# SCH_Trail-PCB_2024-05-27.net
KiCad netlist of a schematic drawn in EasyEDA
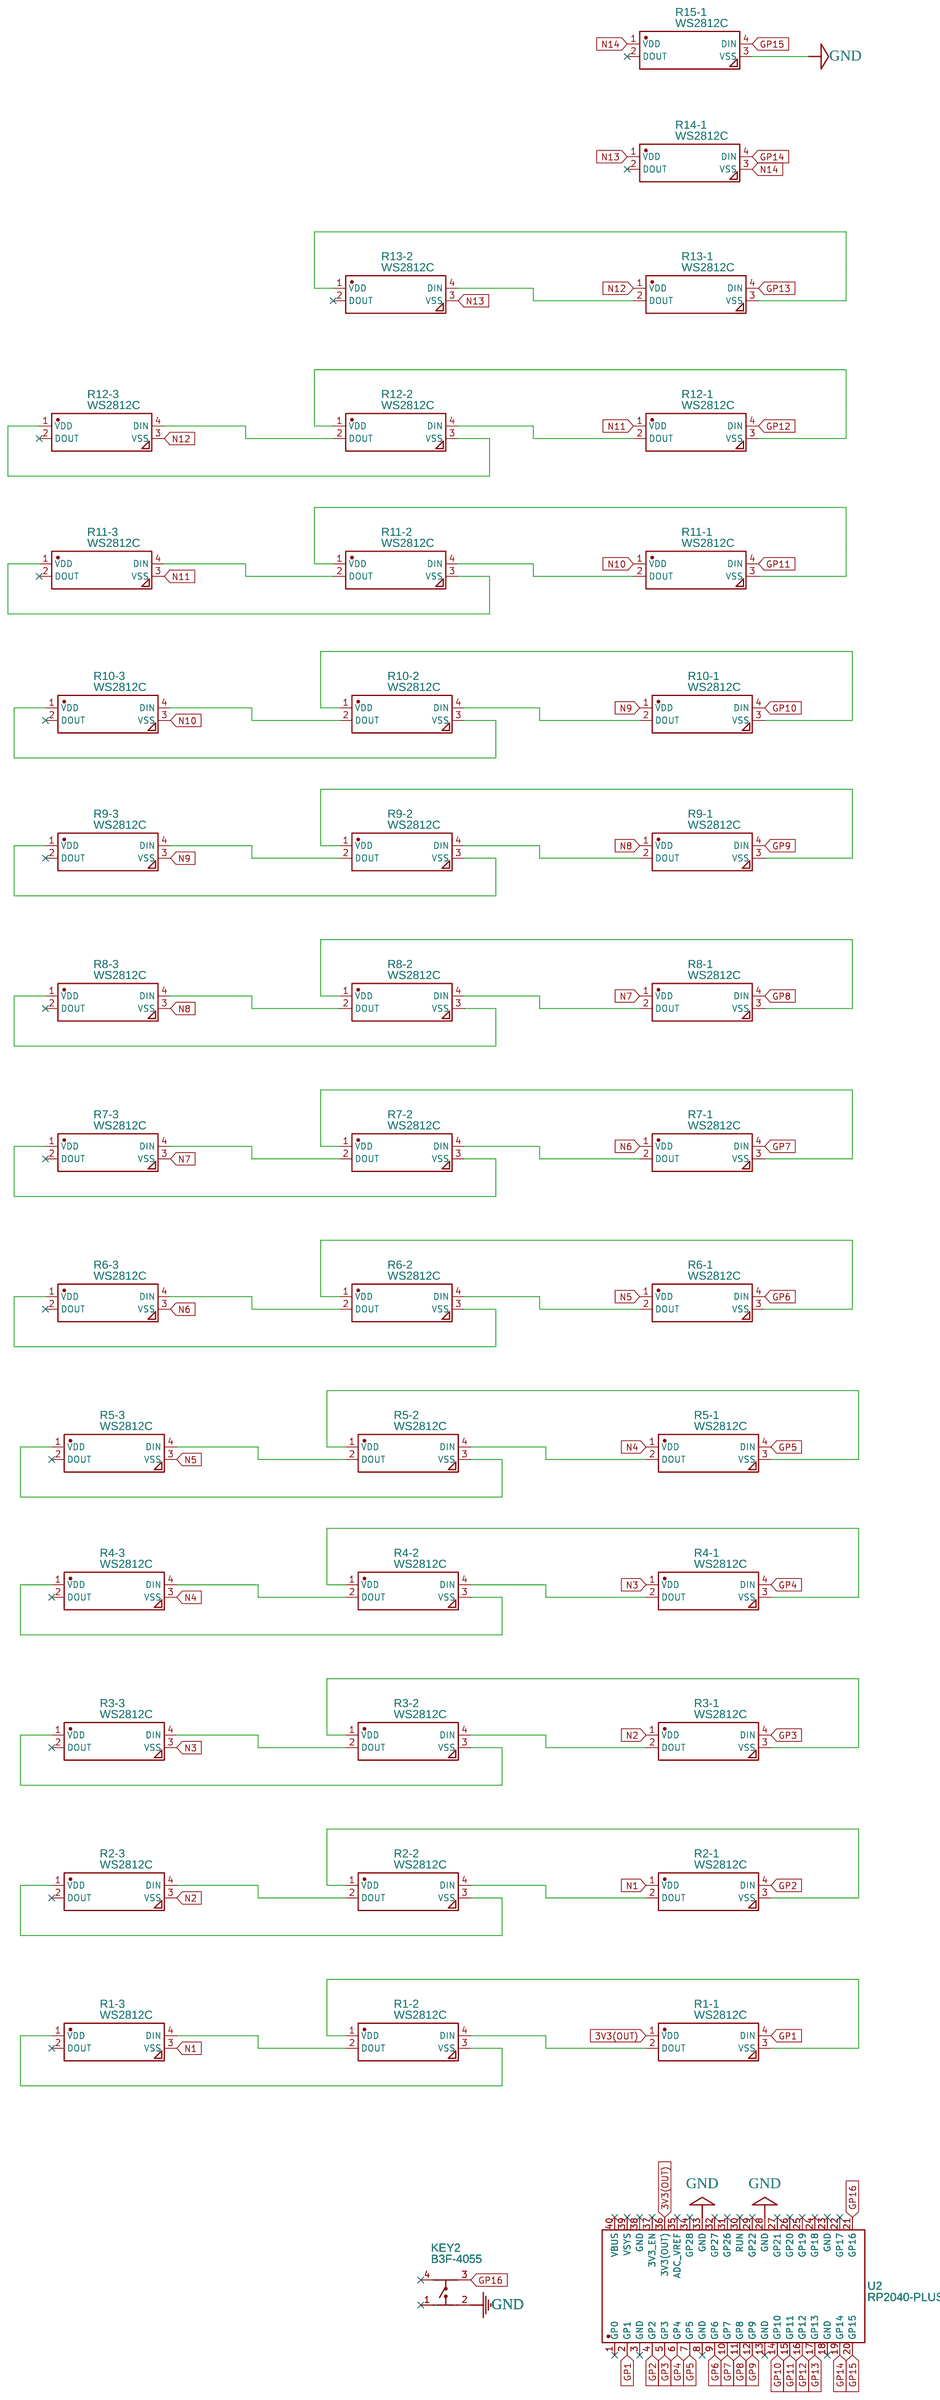
[diagram p0: Sheet_1]
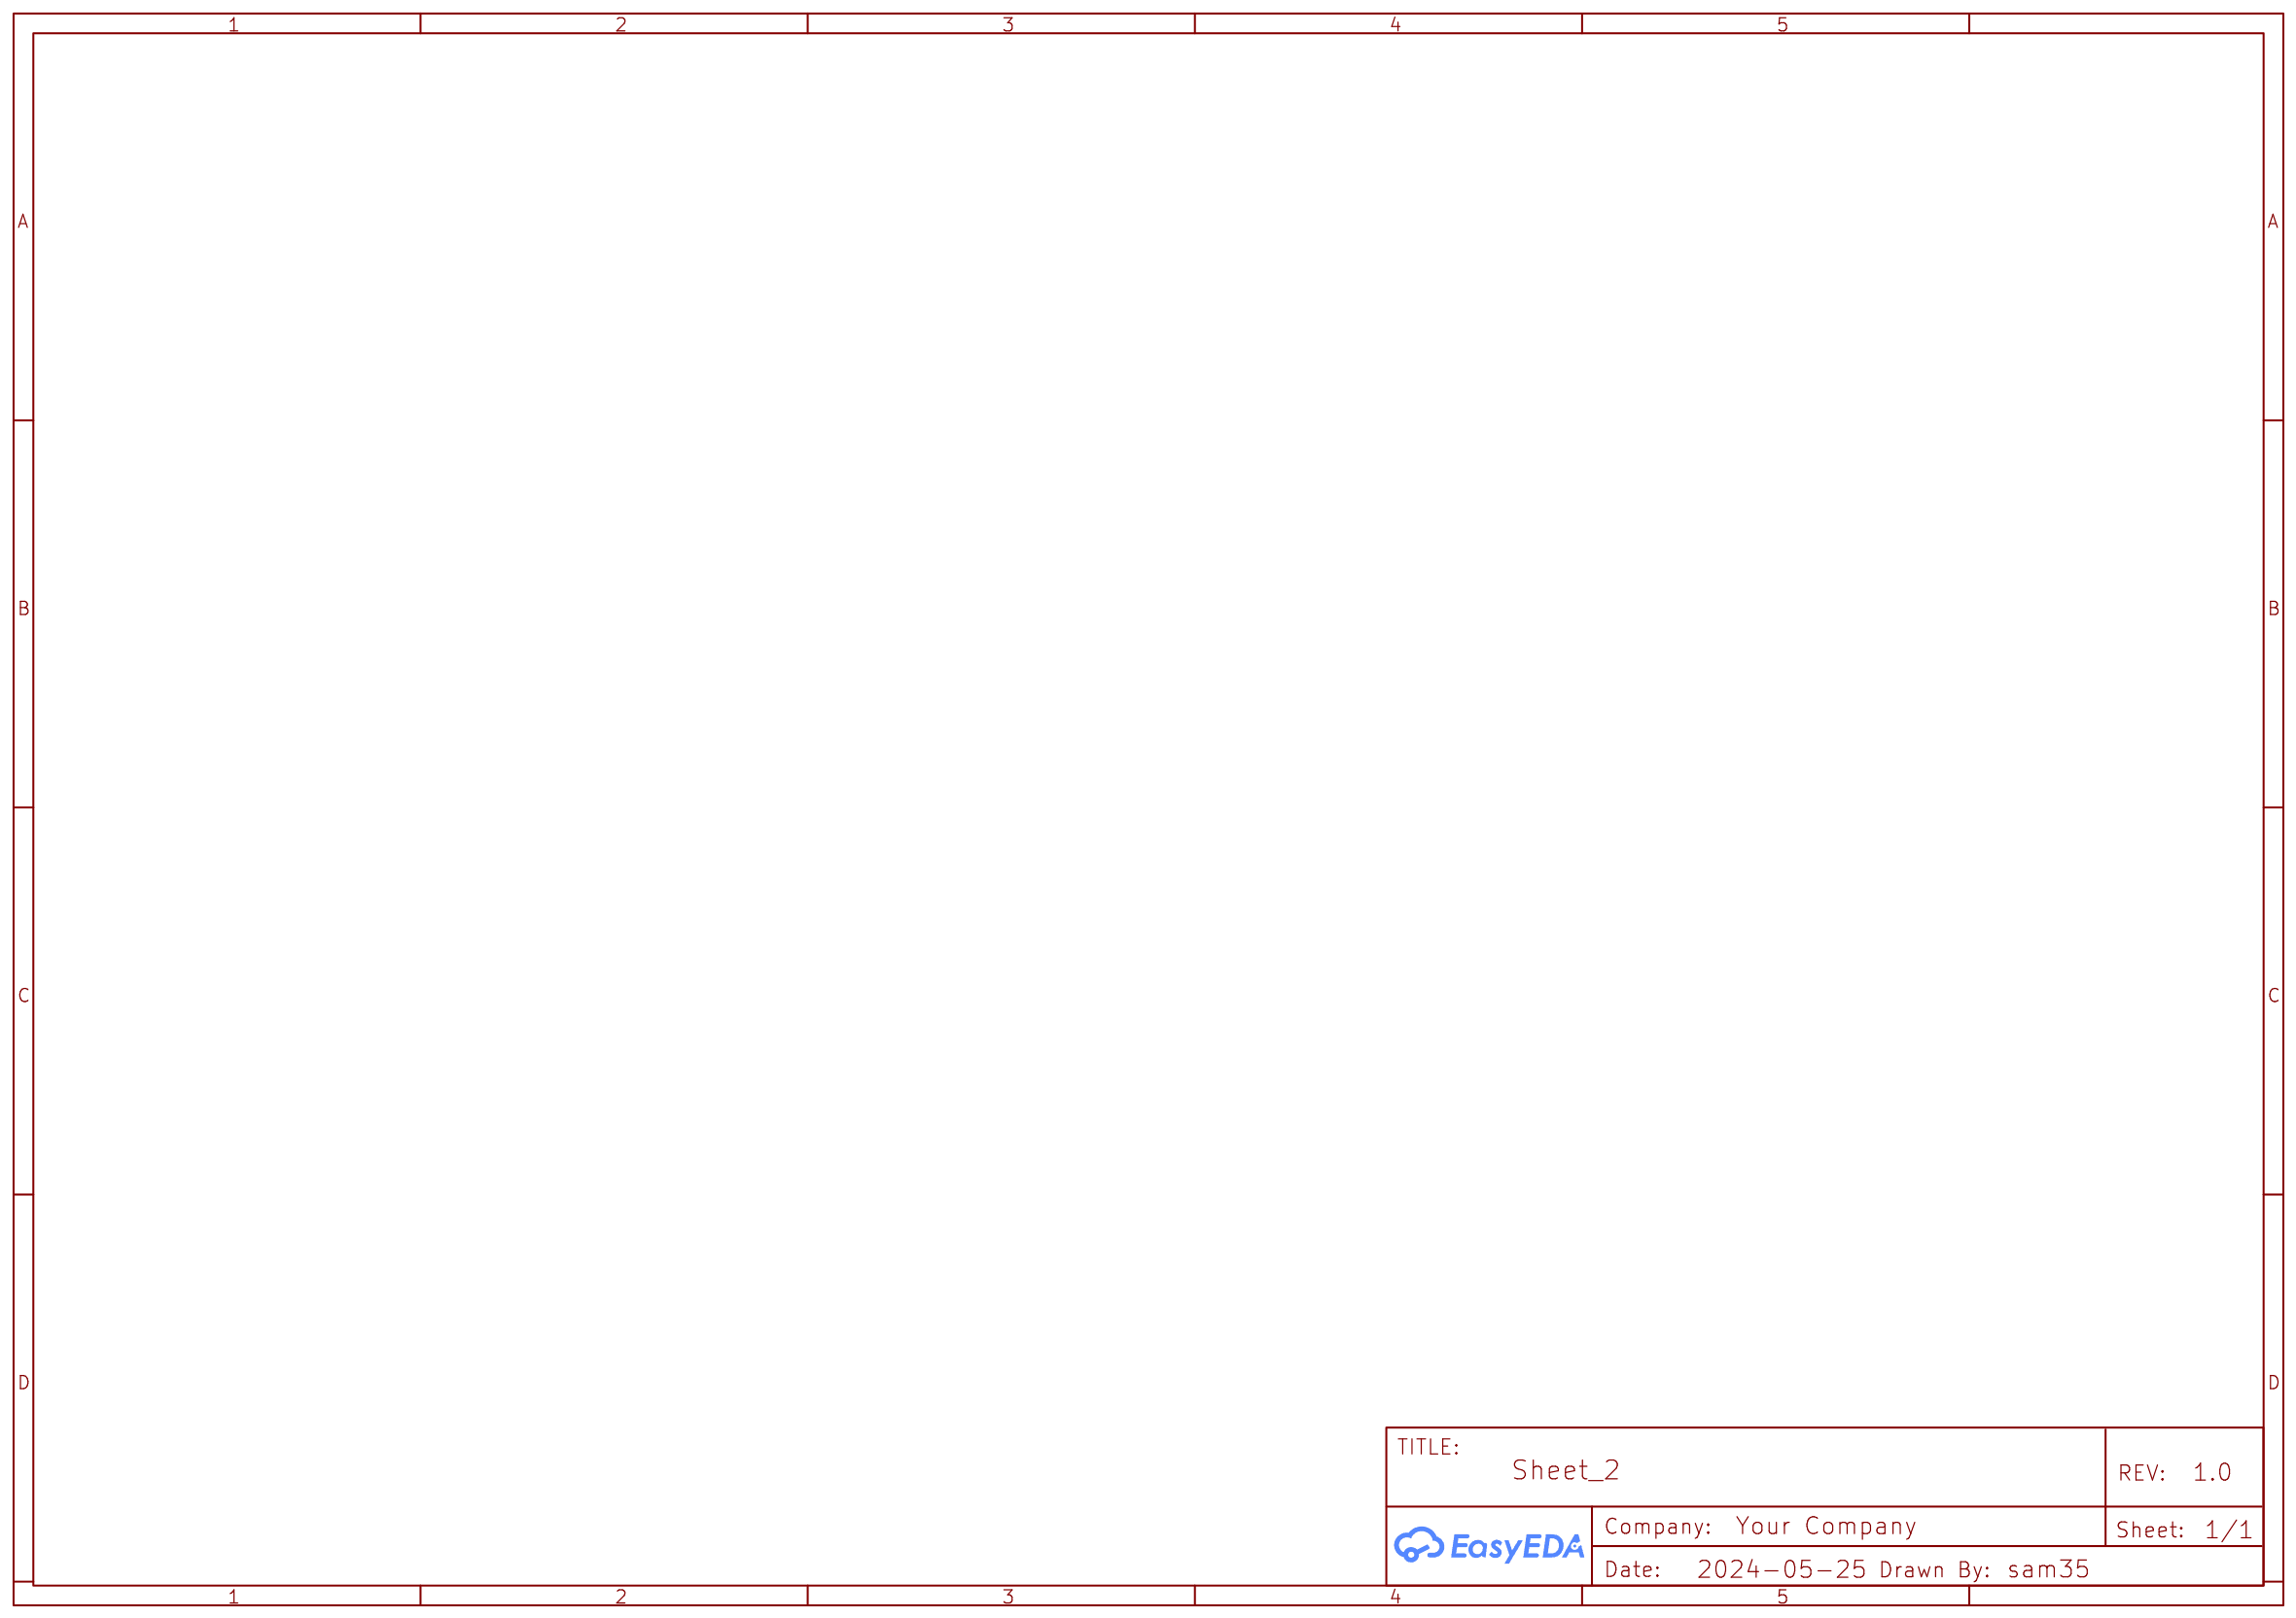
[diagram p1: Sheet_2]

(export (version "E")
  (design (tool "Eeschema 10.0.6"))
  (components
    (comp (ref "KEY2")
      (value "B3F-4055")
      (fields (field (name "Manufacturer") "OMRON(欧姆龙)"))
      (libsource (lib "") (part "B3F-4055"))
    )
    (comp (ref "R1-1")
      (value "WS2812C")
      (fields (field (name "Manufacturer") "worldsemi"))
      (libsource (lib "") (part "WS2812C_4"))
    )
    (comp (ref "R1-2")
      (value "WS2812C")
      (fields (field (name "Manufacturer") "worldsemi"))
      (libsource (lib "") (part "WS2812C_4"))
    )
    (comp (ref "R1-3")
      (value "WS2812C")
      (fields (field (name "Manufacturer") "worldsemi"))
      (libsource (lib "") (part "WS2812C_4"))
    )
    (comp (ref "R2-1")
      (value "WS2812C")
      (fields (field (name "Manufacturer") "worldsemi"))
      (libsource (lib "") (part "WS2812C_8"))
    )
    (comp (ref "R2-2")
      (value "WS2812C")
      (fields (field (name "Manufacturer") "worldsemi"))
      (libsource (lib "") (part "WS2812C_8"))
    )
    (comp (ref "R2-3")
      (value "WS2812C")
      (fields (field (name "Manufacturer") "worldsemi"))
      (libsource (lib "") (part "WS2812C_8"))
    )
    (comp (ref "R3-1")
      (value "WS2812C")
      (fields (field (name "Manufacturer") "worldsemi"))
      (libsource (lib "") (part "WS2812C_3"))
    )
    (comp (ref "R3-2")
      (value "WS2812C")
      (fields (field (name "Manufacturer") "worldsemi"))
      (libsource (lib "") (part "WS2812C_3"))
    )
    (comp (ref "R3-3")
      (value "WS2812C")
      (fields (field (name "Manufacturer") "worldsemi"))
      (libsource (lib "") (part "WS2812C_3"))
    )
    (comp (ref "R4-1")
      (value "WS2812C")
      (fields (field (name "Manufacturer") "worldsemi"))
      (libsource (lib "") (part "WS2812C_6"))
    )
    (comp (ref "R4-2")
      (value "WS2812C")
      (fields (field (name "Manufacturer") "worldsemi"))
      (libsource (lib "") (part "WS2812C_6"))
    )
    (comp (ref "R4-3")
      (value "WS2812C")
      (fields (field (name "Manufacturer") "worldsemi"))
      (libsource (lib "") (part "WS2812C_6"))
    )
    (comp (ref "R5-1")
      (value "WS2812C")
      (fields (field (name "Manufacturer") "worldsemi"))
      (libsource (lib "") (part "WS2812C_1"))
    )
    (comp (ref "R5-2")
      (value "WS2812C")
      (fields (field (name "Manufacturer") "worldsemi"))
      (libsource (lib "") (part "WS2812C_1"))
    )
    (comp (ref "R5-3")
      (value "WS2812C")
      (fields (field (name "Manufacturer") "worldsemi"))
      (libsource (lib "") (part "WS2812C_1"))
    )
    (comp (ref "R6-1")
      (value "WS2812C")
      (fields (field (name "Manufacturer") "worldsemi"))
      (libsource (lib "") (part "WS2812C"))
    )
    (comp (ref "R6-2")
      (value "WS2812C")
      (fields (field (name "Manufacturer") "worldsemi"))
      (libsource (lib "") (part "WS2812C"))
    )
    (comp (ref "R6-3")
      (value "WS2812C")
      (fields (field (name "Manufacturer") "worldsemi"))
      (libsource (lib "") (part "WS2812C"))
    )
    (comp (ref "R7-1")
      (value "WS2812C")
      (fields (field (name "Manufacturer") "worldsemi"))
      (libsource (lib "") (part "WS2812C_7"))
    )
    (comp (ref "R7-2")
      (value "WS2812C")
      (fields (field (name "Manufacturer") "worldsemi"))
      (libsource (lib "") (part "WS2812C_7"))
    )
    (comp (ref "R7-3")
      (value "WS2812C")
      (fields (field (name "Manufacturer") "worldsemi"))
      (libsource (lib "") (part "WS2812C_7"))
    )
    (comp (ref "R8-1")
      (value "WS2812C")
      (fields (field (name "Manufacturer") "worldsemi"))
      (libsource (lib "") (part "WS2812C_9"))
    )
    (comp (ref "R8-2")
      (value "WS2812C")
      (fields (field (name "Manufacturer") "worldsemi"))
      (libsource (lib "") (part "WS2812C_9"))
    )
    (comp (ref "R8-3")
      (value "WS2812C")
      (fields (field (name "Manufacturer") "worldsemi"))
      (libsource (lib "") (part "WS2812C_9"))
    )
    (comp (ref "R9-1")
      (value "WS2812C")
      (fields (field (name "Manufacturer") "worldsemi"))
      (libsource (lib "") (part "WS2812C_11"))
    )
    (comp (ref "R9-2")
      (value "WS2812C")
      (fields (field (name "Manufacturer") "worldsemi"))
      (libsource (lib "") (part "WS2812C_11"))
    )
    (comp (ref "R9-3")
      (value "WS2812C")
      (fields (field (name "Manufacturer") "worldsemi"))
      (libsource (lib "") (part "WS2812C_11"))
    )
    (comp (ref "R10-1")
      (value "WS2812C")
      (fields (field (name "Manufacturer") "worldsemi"))
      (libsource (lib "") (part "WS2812C_12"))
    )
    (comp (ref "R10-2")
      (value "WS2812C")
      (fields (field (name "Manufacturer") "worldsemi"))
      (libsource (lib "") (part "WS2812C_12"))
    )
    (comp (ref "R10-3")
      (value "WS2812C")
      (fields (field (name "Manufacturer") "worldsemi"))
      (libsource (lib "") (part "WS2812C_12"))
    )
    (comp (ref "R11-1")
      (value "WS2812C")
      (fields (field (name "Manufacturer") "worldsemi"))
      (libsource (lib "") (part "WS2812C_2"))
    )
    (comp (ref "R11-2")
      (value "WS2812C")
      (fields (field (name "Manufacturer") "worldsemi"))
      (libsource (lib "") (part "WS2812C_2"))
    )
    (comp (ref "R11-3")
      (value "WS2812C")
      (fields (field (name "Manufacturer") "worldsemi"))
      (libsource (lib "") (part "WS2812C_2"))
    )
    (comp (ref "R12-1")
      (value "WS2812C")
      (fields (field (name "Manufacturer") "worldsemi"))
      (libsource (lib "") (part "WS2812C_5"))
    )
    (comp (ref "R12-2")
      (value "WS2812C")
      (fields (field (name "Manufacturer") "worldsemi"))
      (libsource (lib "") (part "WS2812C_5"))
    )
    (comp (ref "R12-3")
      (value "WS2812C")
      (fields (field (name "Manufacturer") "worldsemi"))
      (libsource (lib "") (part "WS2812C_5"))
    )
    (comp (ref "R13-1")
      (value "WS2812C")
      (fields (field (name "Manufacturer") "worldsemi"))
      (libsource (lib "") (part "WS2812C_13"))
    )
    (comp (ref "R13-2")
      (value "WS2812C")
      (fields (field (name "Manufacturer") "worldsemi"))
      (libsource (lib "") (part "WS2812C_13"))
    )
    (comp (ref "R14-1")
      (value "WS2812C")
      (fields (field (name "Manufacturer") "worldsemi"))
      (libsource (lib "") (part "WS2812C_14"))
    )
    (comp (ref "R15-1")
      (value "WS2812C")
      (fields (field (name "Manufacturer") "worldsemi"))
      (libsource (lib "") (part "WS2812C_10"))
    )
    (comp (ref "U2")
      (value "RP2040-PLUS")
      (fields
        (field (name "Manufacturer Part") "RP2040-Plus")
        (field (name "Manufacturer") "Waveshare(微雪电子)")
      )
      (libsource (lib "") (part "RP2040-PLUS"))
    )
  )
  (nets
    (net (code "1") (name "3V3(OUT)") (class "Default")
      (node (ref "R1-1") (pin "1") (pinfunction "VDD_1") (pintype "unspecified"))
      (node (ref "U2") (pin "36") (pinfunction "3V3(OUT)_36") (pintype "unspecified"))
    )
    (net (code "2") (name "GND") (class "Default")
      (node (ref "KEY2") (pin "2") (pinfunction "2_2") (pintype "unspecified"))
      (node (ref "R15-1") (pin "3") (pinfunction "VSS_3") (pintype "unspecified"))
      (node (ref "U2") (pin "28") (pinfunction "GND_28") (pintype "unspecified"))
      (node (ref "U2") (pin "33") (pinfunction "GND_33") (pintype "unspecified"))
    )
    (net (code "3") (name "GP1") (class "Default")
      (node (ref "R1-1") (pin "4") (pinfunction "DIN_4") (pintype "unspecified"))
      (node (ref "U2") (pin "2") (pinfunction "GP1_2") (pintype "unspecified"))
    )
    (net (code "4") (name "GP2") (class "Default")
      (node (ref "R2-1") (pin "4") (pinfunction "DIN_4") (pintype "unspecified"))
      (node (ref "U2") (pin "4") (pinfunction "GP2_4") (pintype "unspecified"))
    )
    (net (code "5") (name "GP3") (class "Default")
      (node (ref "R3-1") (pin "4") (pinfunction "DIN_4") (pintype "unspecified"))
      (node (ref "U2") (pin "5") (pinfunction "GP3_5") (pintype "unspecified"))
    )
    (net (code "6") (name "GP4") (class "Default")
      (node (ref "R4-1") (pin "4") (pinfunction "DIN_4") (pintype "unspecified"))
      (node (ref "U2") (pin "6") (pinfunction "GP4_6") (pintype "unspecified"))
    )
    (net (code "7") (name "GP5") (class "Default")
      (node (ref "R5-1") (pin "4") (pinfunction "DIN_4") (pintype "unspecified"))
      (node (ref "U2") (pin "7") (pinfunction "GP5_7") (pintype "unspecified"))
    )
    (net (code "8") (name "GP6") (class "Default")
      (node (ref "R6-1") (pin "4") (pinfunction "DIN_4") (pintype "unspecified"))
      (node (ref "U2") (pin "9") (pinfunction "GP6_9") (pintype "unspecified"))
    )
    (net (code "9") (name "GP7") (class "Default")
      (node (ref "R7-1") (pin "4") (pinfunction "DIN_4") (pintype "unspecified"))
      (node (ref "U2") (pin "10") (pinfunction "GP7_10") (pintype "unspecified"))
    )
    (net (code "10") (name "GP8") (class "Default")
      (node (ref "R8-1") (pin "4") (pinfunction "DIN_4") (pintype "unspecified"))
      (node (ref "U2") (pin "11") (pinfunction "GP8_11") (pintype "unspecified"))
    )
    (net (code "11") (name "GP9") (class "Default")
      (node (ref "R9-1") (pin "4") (pinfunction "DIN_4") (pintype "unspecified"))
      (node (ref "U2") (pin "12") (pinfunction "GP9_12") (pintype "unspecified"))
    )
    (net (code "12") (name "GP10") (class "Default")
      (node (ref "R10-1") (pin "4") (pinfunction "DIN_4") (pintype "unspecified"))
      (node (ref "U2") (pin "14") (pinfunction "GP10_14") (pintype "unspecified"))
    )
    (net (code "13") (name "GP11") (class "Default")
      (node (ref "R11-1") (pin "4") (pinfunction "DIN_4") (pintype "unspecified"))
      (node (ref "U2") (pin "15") (pinfunction "GP11_15") (pintype "unspecified"))
    )
    (net (code "14") (name "GP12") (class "Default")
      (node (ref "R12-1") (pin "4") (pinfunction "DIN_4") (pintype "unspecified"))
      (node (ref "U2") (pin "16") (pinfunction "GP12_16") (pintype "unspecified"))
    )
    (net (code "15") (name "GP13") (class "Default")
      (node (ref "R13-1") (pin "4") (pinfunction "DIN_4") (pintype "unspecified"))
      (node (ref "U2") (pin "17") (pinfunction "GP13_17") (pintype "unspecified"))
    )
    (net (code "16") (name "GP14") (class "Default")
      (node (ref "R14-1") (pin "4") (pinfunction "DIN_4") (pintype "unspecified"))
      (node (ref "U2") (pin "19") (pinfunction "GP14_19") (pintype "unspecified"))
    )
    (net (code "17") (name "GP15") (class "Default")
      (node (ref "R15-1") (pin "4") (pinfunction "DIN_4") (pintype "unspecified"))
      (node (ref "U2") (pin "20") (pinfunction "GP15_20") (pintype "unspecified"))
    )
    (net (code "18") (name "GP16") (class "Default")
      (node (ref "KEY2") (pin "3") (pinfunction "3_3") (pintype "unspecified"))
      (node (ref "U2") (pin "21") (pinfunction "GP16_21") (pintype "unspecified"))
    )
    (net (code "19") (name "N1") (class "Default")
      (node (ref "R1-3") (pin "3") (pinfunction "VSS_3") (pintype "unspecified"))
      (node (ref "R2-1") (pin "1") (pinfunction "VDD_1") (pintype "unspecified"))
    )
    (net (code "20") (name "N2") (class "Default")
      (node (ref "R2-3") (pin "3") (pinfunction "VSS_3") (pintype "unspecified"))
      (node (ref "R3-1") (pin "1") (pinfunction "VDD_1") (pintype "unspecified"))
    )
    (net (code "21") (name "N3") (class "Default")
      (node (ref "R3-3") (pin "3") (pinfunction "VSS_3") (pintype "unspecified"))
      (node (ref "R4-1") (pin "1") (pinfunction "VDD_1") (pintype "unspecified"))
    )
    (net (code "22") (name "N4") (class "Default")
      (node (ref "R4-3") (pin "3") (pinfunction "VSS_3") (pintype "unspecified"))
      (node (ref "R5-1") (pin "1") (pinfunction "VDD_1") (pintype "unspecified"))
    )
    (net (code "23") (name "N5") (class "Default")
      (node (ref "R5-3") (pin "3") (pinfunction "VSS_3") (pintype "unspecified"))
      (node (ref "R6-1") (pin "1") (pinfunction "VDD_1") (pintype "unspecified"))
    )
    (net (code "24") (name "N6") (class "Default")
      (node (ref "R6-3") (pin "3") (pinfunction "VSS_3") (pintype "unspecified"))
      (node (ref "R7-1") (pin "1") (pinfunction "VDD_1") (pintype "unspecified"))
    )
    (net (code "25") (name "N7") (class "Default")
      (node (ref "R7-3") (pin "3") (pinfunction "VSS_3") (pintype "unspecified"))
      (node (ref "R8-1") (pin "1") (pinfunction "VDD_1") (pintype "unspecified"))
    )
    (net (code "26") (name "N8") (class "Default")
      (node (ref "R8-3") (pin "3") (pinfunction "VSS_3") (pintype "unspecified"))
      (node (ref "R9-1") (pin "1") (pinfunction "VDD_1") (pintype "unspecified"))
    )
    (net (code "27") (name "N9") (class "Default")
      (node (ref "R10-1") (pin "1") (pinfunction "VDD_1") (pintype "unspecified"))
      (node (ref "R9-3") (pin "3") (pinfunction "VSS_3") (pintype "unspecified"))
    )
    (net (code "28") (name "N10") (class "Default")
      (node (ref "R10-3") (pin "3") (pinfunction "VSS_3") (pintype "unspecified"))
      (node (ref "R11-1") (pin "1") (pinfunction "VDD_1") (pintype "unspecified"))
    )
    (net (code "29") (name "N11") (class "Default")
      (node (ref "R11-3") (pin "3") (pinfunction "VSS_3") (pintype "unspecified"))
      (node (ref "R12-1") (pin "1") (pinfunction "VDD_1") (pintype "unspecified"))
    )
    (net (code "30") (name "N12") (class "Default")
      (node (ref "R12-3") (pin "3") (pinfunction "VSS_3") (pintype "unspecified"))
      (node (ref "R13-1") (pin "1") (pinfunction "VDD_1") (pintype "unspecified"))
    )
    (net (code "31") (name "N13") (class "Default")
      (node (ref "R13-2") (pin "3") (pinfunction "VSS_3") (pintype "unspecified"))
      (node (ref "R14-1") (pin "1") (pinfunction "VDD_1") (pintype "unspecified"))
    )
    (net (code "32") (name "N14") (class "Default")
      (node (ref "R14-1") (pin "3") (pinfunction "VSS_3") (pintype "unspecified"))
      (node (ref "R15-1") (pin "1") (pinfunction "VDD_1") (pintype "unspecified"))
    )
    (net (code "33") (name "Net-(R1-1-DOUT)") (class "Default")
      (node (ref "R1-1") (pin "2") (pinfunction "DOUT_2") (pintype "unspecified"))
      (node (ref "R1-2") (pin "4") (pinfunction "DIN_4") (pintype "unspecified"))
    )
    (net (code "34") (name "Net-(R1-1-VSS)") (class "Default")
      (node (ref "R1-1") (pin "3") (pinfunction "VSS_3") (pintype "unspecified"))
      (node (ref "R1-2") (pin "1") (pinfunction "VDD_1") (pintype "unspecified"))
    )
    (net (code "35") (name "Net-(R1-2-DOUT)") (class "Default")
      (node (ref "R1-2") (pin "2") (pinfunction "DOUT_2") (pintype "unspecified"))
      (node (ref "R1-3") (pin "4") (pinfunction "DIN_4") (pintype "unspecified"))
    )
    (net (code "36") (name "Net-(R1-2-VSS)") (class "Default")
      (node (ref "R1-2") (pin "3") (pinfunction "VSS_3") (pintype "unspecified"))
      (node (ref "R1-3") (pin "1") (pinfunction "VDD_1") (pintype "unspecified"))
    )
    (net (code "37") (name "Net-(R2-1-DOUT)") (class "Default")
      (node (ref "R2-1") (pin "2") (pinfunction "DOUT_2") (pintype "unspecified"))
      (node (ref "R2-2") (pin "4") (pinfunction "DIN_4") (pintype "unspecified"))
    )
    (net (code "38") (name "Net-(R2-1-VSS)") (class "Default")
      (node (ref "R2-1") (pin "3") (pinfunction "VSS_3") (pintype "unspecified"))
      (node (ref "R2-2") (pin "1") (pinfunction "VDD_1") (pintype "unspecified"))
    )
    (net (code "39") (name "Net-(R2-2-DOUT)") (class "Default")
      (node (ref "R2-2") (pin "2") (pinfunction "DOUT_2") (pintype "unspecified"))
      (node (ref "R2-3") (pin "4") (pinfunction "DIN_4") (pintype "unspecified"))
    )
    (net (code "40") (name "Net-(R2-2-VSS)") (class "Default")
      (node (ref "R2-2") (pin "3") (pinfunction "VSS_3") (pintype "unspecified"))
      (node (ref "R2-3") (pin "1") (pinfunction "VDD_1") (pintype "unspecified"))
    )
    (net (code "41") (name "Net-(R3-1-DOUT)") (class "Default")
      (node (ref "R3-1") (pin "2") (pinfunction "DOUT_2") (pintype "unspecified"))
      (node (ref "R3-2") (pin "4") (pinfunction "DIN_4") (pintype "unspecified"))
    )
    (net (code "42") (name "Net-(R3-1-VSS)") (class "Default")
      (node (ref "R3-1") (pin "3") (pinfunction "VSS_3") (pintype "unspecified"))
      (node (ref "R3-2") (pin "1") (pinfunction "VDD_1") (pintype "unspecified"))
    )
    (net (code "43") (name "Net-(R3-2-DOUT)") (class "Default")
      (node (ref "R3-2") (pin "2") (pinfunction "DOUT_2") (pintype "unspecified"))
      (node (ref "R3-3") (pin "4") (pinfunction "DIN_4") (pintype "unspecified"))
    )
    (net (code "44") (name "Net-(R3-2-VSS)") (class "Default")
      (node (ref "R3-2") (pin "3") (pinfunction "VSS_3") (pintype "unspecified"))
      (node (ref "R3-3") (pin "1") (pinfunction "VDD_1") (pintype "unspecified"))
    )
    (net (code "45") (name "Net-(R4-1-DOUT)") (class "Default")
      (node (ref "R4-1") (pin "2") (pinfunction "DOUT_2") (pintype "unspecified"))
      (node (ref "R4-2") (pin "4") (pinfunction "DIN_4") (pintype "unspecified"))
    )
    (net (code "46") (name "Net-(R4-1-VSS)") (class "Default")
      (node (ref "R4-1") (pin "3") (pinfunction "VSS_3") (pintype "unspecified"))
      (node (ref "R4-2") (pin "1") (pinfunction "VDD_1") (pintype "unspecified"))
    )
    (net (code "47") (name "Net-(R4-2-DOUT)") (class "Default")
      (node (ref "R4-2") (pin "2") (pinfunction "DOUT_2") (pintype "unspecified"))
      (node (ref "R4-3") (pin "4") (pinfunction "DIN_4") (pintype "unspecified"))
    )
    (net (code "48") (name "Net-(R4-2-VSS)") (class "Default")
      (node (ref "R4-2") (pin "3") (pinfunction "VSS_3") (pintype "unspecified"))
      (node (ref "R4-3") (pin "1") (pinfunction "VDD_1") (pintype "unspecified"))
    )
    (net (code "49") (name "Net-(R5-1-DOUT)") (class "Default")
      (node (ref "R5-1") (pin "2") (pinfunction "DOUT_2") (pintype "unspecified"))
      (node (ref "R5-2") (pin "4") (pinfunction "DIN_4") (pintype "unspecified"))
    )
    (net (code "50") (name "Net-(R5-1-VSS)") (class "Default")
      (node (ref "R5-1") (pin "3") (pinfunction "VSS_3") (pintype "unspecified"))
      (node (ref "R5-2") (pin "1") (pinfunction "VDD_1") (pintype "unspecified"))
    )
    (net (code "51") (name "Net-(R5-2-DOUT)") (class "Default")
      (node (ref "R5-2") (pin "2") (pinfunction "DOUT_2") (pintype "unspecified"))
      (node (ref "R5-3") (pin "4") (pinfunction "DIN_4") (pintype "unspecified"))
    )
    (net (code "52") (name "Net-(R5-2-VSS)") (class "Default")
      (node (ref "R5-2") (pin "3") (pinfunction "VSS_3") (pintype "unspecified"))
      (node (ref "R5-3") (pin "1") (pinfunction "VDD_1") (pintype "unspecified"))
    )
    (net (code "53") (name "Net-(R6-1-DOUT)") (class "Default")
      (node (ref "R6-1") (pin "2") (pinfunction "DOUT_2") (pintype "unspecified"))
      (node (ref "R6-2") (pin "4") (pinfunction "DIN_4") (pintype "unspecified"))
    )
    (net (code "54") (name "Net-(R6-1-VSS)") (class "Default")
      (node (ref "R6-1") (pin "3") (pinfunction "VSS_3") (pintype "unspecified"))
      (node (ref "R6-2") (pin "1") (pinfunction "VDD_1") (pintype "unspecified"))
    )
    (net (code "55") (name "Net-(R6-2-DOUT)") (class "Default")
      (node (ref "R6-2") (pin "2") (pinfunction "DOUT_2") (pintype "unspecified"))
      (node (ref "R6-3") (pin "4") (pinfunction "DIN_4") (pintype "unspecified"))
    )
    (net (code "56") (name "Net-(R6-2-VSS)") (class "Default")
      (node (ref "R6-2") (pin "3") (pinfunction "VSS_3") (pintype "unspecified"))
      (node (ref "R6-3") (pin "1") (pinfunction "VDD_1") (pintype "unspecified"))
    )
    (net (code "57") (name "Net-(R7-1-DOUT)") (class "Default")
      (node (ref "R7-1") (pin "2") (pinfunction "DOUT_2") (pintype "unspecified"))
      (node (ref "R7-2") (pin "4") (pinfunction "DIN_4") (pintype "unspecified"))
    )
    (net (code "58") (name "Net-(R7-1-VSS)") (class "Default")
      (node (ref "R7-1") (pin "3") (pinfunction "VSS_3") (pintype "unspecified"))
      (node (ref "R7-2") (pin "1") (pinfunction "VDD_1") (pintype "unspecified"))
    )
    (net (code "59") (name "Net-(R7-2-DOUT)") (class "Default")
      (node (ref "R7-2") (pin "2") (pinfunction "DOUT_2") (pintype "unspecified"))
      (node (ref "R7-3") (pin "4") (pinfunction "DIN_4") (pintype "unspecified"))
    )
    (net (code "60") (name "Net-(R7-2-VSS)") (class "Default")
      (node (ref "R7-2") (pin "3") (pinfunction "VSS_3") (pintype "unspecified"))
      (node (ref "R7-3") (pin "1") (pinfunction "VDD_1") (pintype "unspecified"))
    )
    (net (code "61") (name "Net-(R8-1-DOUT)") (class "Default")
      (node (ref "R8-1") (pin "2") (pinfunction "DOUT_2") (pintype "unspecified"))
      (node (ref "R8-2") (pin "4") (pinfunction "DIN_4") (pintype "unspecified"))
    )
    (net (code "62") (name "Net-(R8-1-VSS)") (class "Default")
      (node (ref "R8-1") (pin "3") (pinfunction "VSS_3") (pintype "unspecified"))
      (node (ref "R8-2") (pin "1") (pinfunction "VDD_1") (pintype "unspecified"))
    )
    (net (code "63") (name "Net-(R8-2-DOUT)") (class "Default")
      (node (ref "R8-2") (pin "2") (pinfunction "DOUT_2") (pintype "unspecified"))
      (node (ref "R8-3") (pin "4") (pinfunction "DIN_4") (pintype "unspecified"))
    )
    (net (code "64") (name "Net-(R8-2-VSS)") (class "Default")
      (node (ref "R8-2") (pin "3") (pinfunction "VSS_3") (pintype "unspecified"))
      (node (ref "R8-3") (pin "1") (pinfunction "VDD_1") (pintype "unspecified"))
    )
    (net (code "65") (name "Net-(R9-1-DOUT)") (class "Default")
      (node (ref "R9-1") (pin "2") (pinfunction "DOUT_2") (pintype "unspecified"))
      (node (ref "R9-2") (pin "4") (pinfunction "DIN_4") (pintype "unspecified"))
    )
    (net (code "66") (name "Net-(R9-1-VSS)") (class "Default")
      (node (ref "R9-1") (pin "3") (pinfunction "VSS_3") (pintype "unspecified"))
      (node (ref "R9-2") (pin "1") (pinfunction "VDD_1") (pintype "unspecified"))
    )
    (net (code "67") (name "Net-(R9-2-DOUT)") (class "Default")
      (node (ref "R9-2") (pin "2") (pinfunction "DOUT_2") (pintype "unspecified"))
      (node (ref "R9-3") (pin "4") (pinfunction "DIN_4") (pintype "unspecified"))
    )
    (net (code "68") (name "Net-(R9-2-VSS)") (class "Default")
      (node (ref "R9-2") (pin "3") (pinfunction "VSS_3") (pintype "unspecified"))
      (node (ref "R9-3") (pin "1") (pinfunction "VDD_1") (pintype "unspecified"))
    )
    (net (code "69") (name "Net-(R10-1-DOUT)") (class "Default")
      (node (ref "R10-1") (pin "2") (pinfunction "DOUT_2") (pintype "unspecified"))
      (node (ref "R10-2") (pin "4") (pinfunction "DIN_4") (pintype "unspecified"))
    )
    (net (code "70") (name "Net-(R10-1-VSS)") (class "Default")
      (node (ref "R10-1") (pin "3") (pinfunction "VSS_3") (pintype "unspecified"))
      (node (ref "R10-2") (pin "1") (pinfunction "VDD_1") (pintype "unspecified"))
    )
    (net (code "71") (name "Net-(R10-2-DOUT)") (class "Default")
      (node (ref "R10-2") (pin "2") (pinfunction "DOUT_2") (pintype "unspecified"))
      (node (ref "R10-3") (pin "4") (pinfunction "DIN_4") (pintype "unspecified"))
    )
    (net (code "72") (name "Net-(R10-2-VSS)") (class "Default")
      (node (ref "R10-2") (pin "3") (pinfunction "VSS_3") (pintype "unspecified"))
      (node (ref "R10-3") (pin "1") (pinfunction "VDD_1") (pintype "unspecified"))
    )
    (net (code "73") (name "Net-(R11-1-DOUT)") (class "Default")
      (node (ref "R11-1") (pin "2") (pinfunction "DOUT_2") (pintype "unspecified"))
      (node (ref "R11-2") (pin "4") (pinfunction "DIN_4") (pintype "unspecified"))
    )
    (net (code "74") (name "Net-(R11-1-VSS)") (class "Default")
      (node (ref "R11-1") (pin "3") (pinfunction "VSS_3") (pintype "unspecified"))
      (node (ref "R11-2") (pin "1") (pinfunction "VDD_1") (pintype "unspecified"))
    )
    (net (code "75") (name "Net-(R11-2-DOUT)") (class "Default")
      (node (ref "R11-2") (pin "2") (pinfunction "DOUT_2") (pintype "unspecified"))
      (node (ref "R11-3") (pin "4") (pinfunction "DIN_4") (pintype "unspecified"))
    )
    (net (code "76") (name "Net-(R11-2-VSS)") (class "Default")
      (node (ref "R11-2") (pin "3") (pinfunction "VSS_3") (pintype "unspecified"))
      (node (ref "R11-3") (pin "1") (pinfunction "VDD_1") (pintype "unspecified"))
    )
    (net (code "77") (name "Net-(R12-1-DOUT)") (class "Default")
      (node (ref "R12-1") (pin "2") (pinfunction "DOUT_2") (pintype "unspecified"))
      (node (ref "R12-2") (pin "4") (pinfunction "DIN_4") (pintype "unspecified"))
    )
    (net (code "78") (name "Net-(R12-1-VSS)") (class "Default")
      (node (ref "R12-1") (pin "3") (pinfunction "VSS_3") (pintype "unspecified"))
      (node (ref "R12-2") (pin "1") (pinfunction "VDD_1") (pintype "unspecified"))
    )
    (net (code "79") (name "Net-(R12-2-DOUT)") (class "Default")
      (node (ref "R12-2") (pin "2") (pinfunction "DOUT_2") (pintype "unspecified"))
      (node (ref "R12-3") (pin "4") (pinfunction "DIN_4") (pintype "unspecified"))
    )
    (net (code "80") (name "Net-(R12-2-VSS)") (class "Default")
      (node (ref "R12-2") (pin "3") (pinfunction "VSS_3") (pintype "unspecified"))
      (node (ref "R12-3") (pin "1") (pinfunction "VDD_1") (pintype "unspecified"))
    )
    (net (code "81") (name "Net-(R13-1-DOUT)") (class "Default")
      (node (ref "R13-1") (pin "2") (pinfunction "DOUT_2") (pintype "unspecified"))
      (node (ref "R13-2") (pin "4") (pinfunction "DIN_4") (pintype "unspecified"))
    )
    (net (code "82") (name "Net-(R13-1-VSS)") (class "Default")
      (node (ref "R13-1") (pin "3") (pinfunction "VSS_3") (pintype "unspecified"))
      (node (ref "R13-2") (pin "1") (pinfunction "VDD_1") (pintype "unspecified"))
    )
    (net (code "83") (name "unconnected-(KEY2-Pad1)") (class "Default")
      (node (ref "KEY2") (pin "1") (pinfunction "1_1") (pintype "unspecified+no_connect"))
    )
    (net (code "84") (name "unconnected-(KEY2-Pad4)") (class "Default")
      (node (ref "KEY2") (pin "4") (pinfunction "4_4") (pintype "unspecified+no_connect"))
    )
    (net (code "85") (name "unconnected-(R1-3-DOUT-Pad2)") (class "Default")
      (node (ref "R1-3") (pin "2") (pinfunction "DOUT_2") (pintype "unspecified+no_connect"))
    )
    (net (code "86") (name "unconnected-(R2-3-DOUT-Pad2)") (class "Default")
      (node (ref "R2-3") (pin "2") (pinfunction "DOUT_2") (pintype "unspecified+no_connect"))
    )
    (net (code "87") (name "unconnected-(R3-3-DOUT-Pad2)") (class "Default")
      (node (ref "R3-3") (pin "2") (pinfunction "DOUT_2") (pintype "unspecified+no_connect"))
    )
    (net (code "88") (name "unconnected-(R4-3-DOUT-Pad2)") (class "Default")
      (node (ref "R4-3") (pin "2") (pinfunction "DOUT_2") (pintype "unspecified+no_connect"))
    )
    (net (code "89") (name "unconnected-(R5-3-DOUT-Pad2)") (class "Default")
      (node (ref "R5-3") (pin "2") (pinfunction "DOUT_2") (pintype "unspecified+no_connect"))
    )
    (net (code "90") (name "unconnected-(R6-3-DOUT-Pad2)") (class "Default")
      (node (ref "R6-3") (pin "2") (pinfunction "DOUT_2") (pintype "unspecified+no_connect"))
    )
    (net (code "91") (name "unconnected-(R7-3-DOUT-Pad2)") (class "Default")
      (node (ref "R7-3") (pin "2") (pinfunction "DOUT_2") (pintype "unspecified+no_connect"))
    )
    (net (code "92") (name "unconnected-(R8-3-DOUT-Pad2)") (class "Default")
      (node (ref "R8-3") (pin "2") (pinfunction "DOUT_2") (pintype "unspecified+no_connect"))
    )
    (net (code "93") (name "unconnected-(R9-3-DOUT-Pad2)") (class "Default")
      (node (ref "R9-3") (pin "2") (pinfunction "DOUT_2") (pintype "unspecified+no_connect"))
    )
    (net (code "94") (name "unconnected-(R10-3-DOUT-Pad2)") (class "Default")
      (node (ref "R10-3") (pin "2") (pinfunction "DOUT_2") (pintype "unspecified+no_connect"))
    )
    (net (code "95") (name "unconnected-(R11-3-DOUT-Pad2)") (class "Default")
      (node (ref "R11-3") (pin "2") (pinfunction "DOUT_2") (pintype "unspecified+no_connect"))
    )
    (net (code "96") (name "unconnected-(R12-3-DOUT-Pad2)") (class "Default")
      (node (ref "R12-3") (pin "2") (pinfunction "DOUT_2") (pintype "unspecified+no_connect"))
    )
    (net (code "97") (name "unconnected-(R13-2-DOUT-Pad2)") (class "Default")
      (node (ref "R13-2") (pin "2") (pinfunction "DOUT_2") (pintype "unspecified+no_connect"))
    )
    (net (code "98") (name "unconnected-(R14-1-DOUT-Pad2)") (class "Default")
      (node (ref "R14-1") (pin "2") (pinfunction "DOUT_2") (pintype "unspecified+no_connect"))
    )
    (net (code "99") (name "unconnected-(R15-1-DOUT-Pad2)") (class "Default")
      (node (ref "R15-1") (pin "2") (pinfunction "DOUT_2") (pintype "unspecified+no_connect"))
    )
    (net (code "100") (name "unconnected-(U2-3V3_EN-Pad37)") (class "Default")
      (node (ref "U2") (pin "37") (pinfunction "3V3_EN_37") (pintype "unspecified+no_connect"))
    )
    (net (code "101") (name "unconnected-(U2-ADC_VREF-Pad35)") (class "Default")
      (node (ref "U2") (pin "35") (pinfunction "ADC_VREF_35") (pintype "unspecified+no_connect"))
    )
    (net (code "102") (name "unconnected-(U2-GND-Pad3)") (class "Default")
      (node (ref "U2") (pin "3") (pinfunction "GND_3") (pintype "unspecified+no_connect"))
    )
    (net (code "103") (name "unconnected-(U2-GND-Pad8)") (class "Default")
      (node (ref "U2") (pin "8") (pinfunction "GND_8") (pintype "unspecified+no_connect"))
    )
    (net (code "104") (name "unconnected-(U2-GND-Pad13)") (class "Default")
      (node (ref "U2") (pin "13") (pinfunction "GND_13") (pintype "unspecified+no_connect"))
    )
    (net (code "105") (name "unconnected-(U2-GND-Pad18)") (class "Default")
      (node (ref "U2") (pin "18") (pinfunction "GND_18") (pintype "unspecified+no_connect"))
    )
    (net (code "106") (name "unconnected-(U2-GND-Pad23)") (class "Default")
      (node (ref "U2") (pin "23") (pinfunction "GND_23") (pintype "unspecified+no_connect"))
    )
    (net (code "107") (name "unconnected-(U2-GND-Pad38)") (class "Default")
      (node (ref "U2") (pin "38") (pinfunction "GND_38") (pintype "unspecified+no_connect"))
    )
    (net (code "108") (name "unconnected-(U2-GP0-Pad1)") (class "Default")
      (node (ref "U2") (pin "1") (pinfunction "GP0_1") (pintype "unspecified+no_connect"))
    )
    (net (code "109") (name "unconnected-(U2-GP17-Pad22)") (class "Default")
      (node (ref "U2") (pin "22") (pinfunction "GP17_22") (pintype "unspecified+no_connect"))
    )
    (net (code "110") (name "unconnected-(U2-GP18-Pad24)") (class "Default")
      (node (ref "U2") (pin "24") (pinfunction "GP18_24") (pintype "unspecified+no_connect"))
    )
    (net (code "111") (name "unconnected-(U2-GP19-Pad25)") (class "Default")
      (node (ref "U2") (pin "25") (pinfunction "GP19_25") (pintype "unspecified+no_connect"))
    )
    (net (code "112") (name "unconnected-(U2-GP20-Pad26)") (class "Default")
      (node (ref "U2") (pin "26") (pinfunction "GP20_26") (pintype "unspecified+no_connect"))
    )
    (net (code "113") (name "unconnected-(U2-GP21-Pad27)") (class "Default")
      (node (ref "U2") (pin "27") (pinfunction "GP21_27") (pintype "unspecified+no_connect"))
    )
    (net (code "114") (name "unconnected-(U2-GP22-Pad29)") (class "Default")
      (node (ref "U2") (pin "29") (pinfunction "GP22_29") (pintype "unspecified+no_connect"))
    )
    (net (code "115") (name "unconnected-(U2-GP26-Pad31)") (class "Default")
      (node (ref "U2") (pin "31") (pinfunction "GP26_31") (pintype "unspecified+no_connect"))
    )
    (net (code "116") (name "unconnected-(U2-GP27-Pad32)") (class "Default")
      (node (ref "U2") (pin "32") (pinfunction "GP27_32") (pintype "unspecified+no_connect"))
    )
    (net (code "117") (name "unconnected-(U2-GP28-Pad34)") (class "Default")
      (node (ref "U2") (pin "34") (pinfunction "GP28_34") (pintype "unspecified+no_connect"))
    )
    (net (code "118") (name "unconnected-(U2-RUN-Pad30)") (class "Default")
      (node (ref "U2") (pin "30") (pinfunction "RUN_30") (pintype "unspecified+no_connect"))
    )
    (net (code "119") (name "unconnected-(U2-VBUS-Pad40)") (class "Default")
      (node (ref "U2") (pin "40") (pinfunction "VBUS_40") (pintype "unspecified+no_connect"))
    )
    (net (code "120") (name "unconnected-(U2-VSYS-Pad39)") (class "Default")
      (node (ref "U2") (pin "39") (pinfunction "VSYS_39") (pintype "unspecified+no_connect"))
    )
  )
)
